# 1A19J5_1A20J9_A.net
KiCad netlist of a schematic drawn in Altium Designer
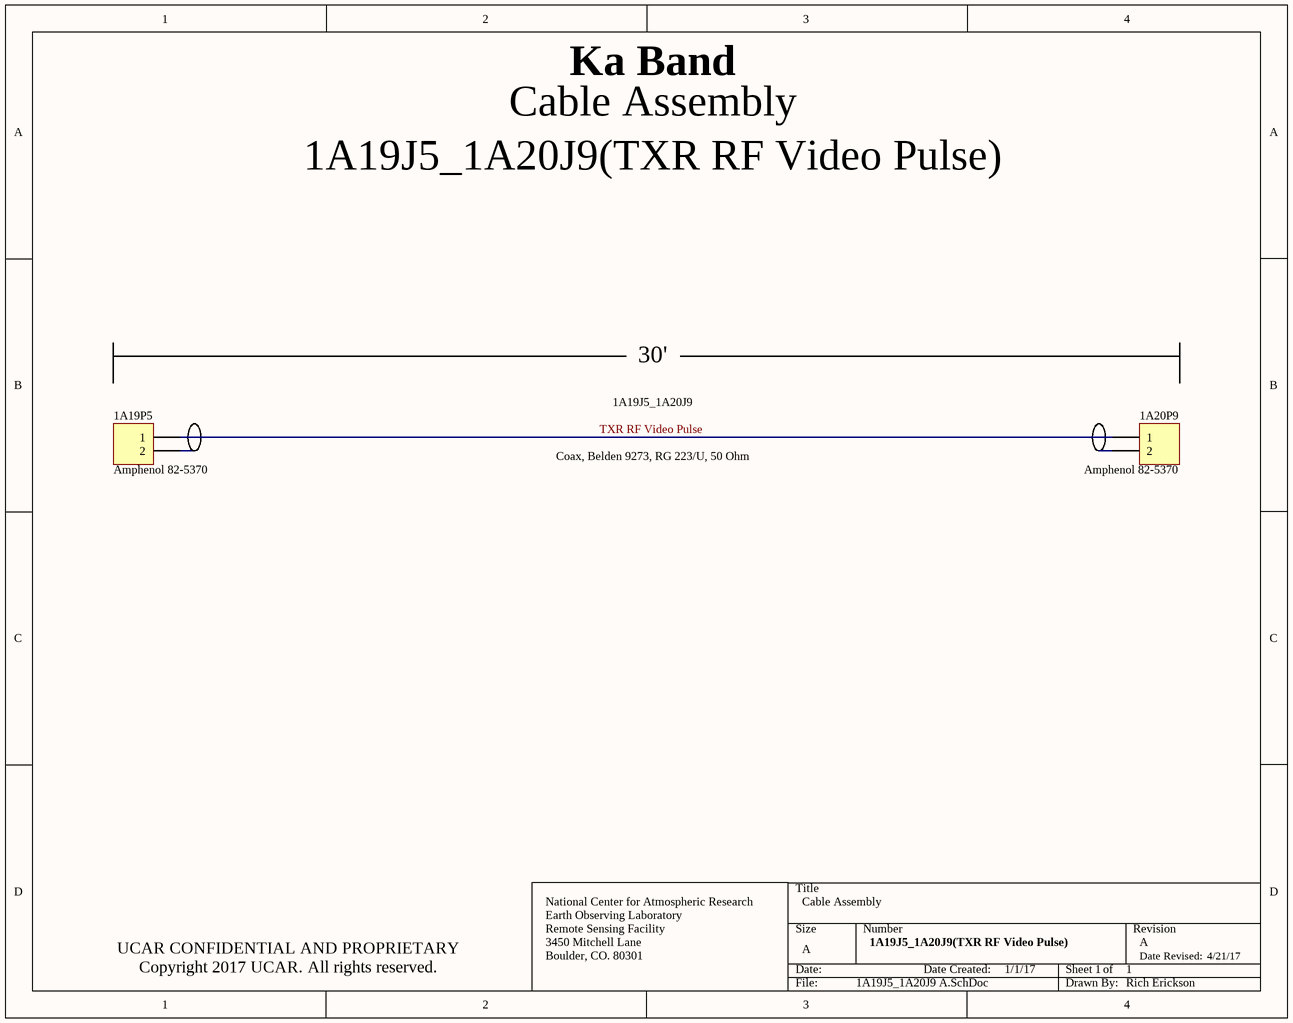
[diagram p0: 1A19J5_1A20J9 A.SchDoc]

(export (version "E")
  (design (tool "Eeschema 10.0.6"))
  (components
    (comp (ref "1A19P5")
      (value "Amphenol 82-5370")
      (footprint "HDR1X2")
      (description "Header, 2-Pin")
      (fields (field (name "PUBLISHER") "Altium Limited"))
      (libsource (lib "") (part "Header 2_1"))
    )
    (comp (ref "1A20P9")
      (value "Amphenol 82-5370")
      (footprint "HDR1X2")
      (description "Header, 2-Pin")
      (fields (field (name "PUBLISHER") "Altium Limited"))
      (libsource (lib "Miscellaneous Connectors") (part "Header 2"))
    )
  )
  (nets
    (net (code "1") (name "/TXR RF Video Pulse") (class "Default")
      (node (ref "1A19P5") (pin "1") (pinfunction "1_1") (pintype "passive"))
      (node (ref "1A20P9") (pin "1") (pinfunction "1_1") (pintype "passive"))
    )
    (net (code "2") (name "unconnected-(1A19P5-Pad2)") (class "Default")
      (node (ref "1A19P5") (pin "2") (pinfunction "2_2") (pintype "passive"))
    )
    (net (code "3") (name "unconnected-(1A20P9-Pad2)") (class "Default")
      (node (ref "1A20P9") (pin "2") (pinfunction "2_2") (pintype "passive"))
    )
  )
)
